# ThrowBot_RX_LED_Board.net
KiCad netlist of a schematic drawn in Altium Designer
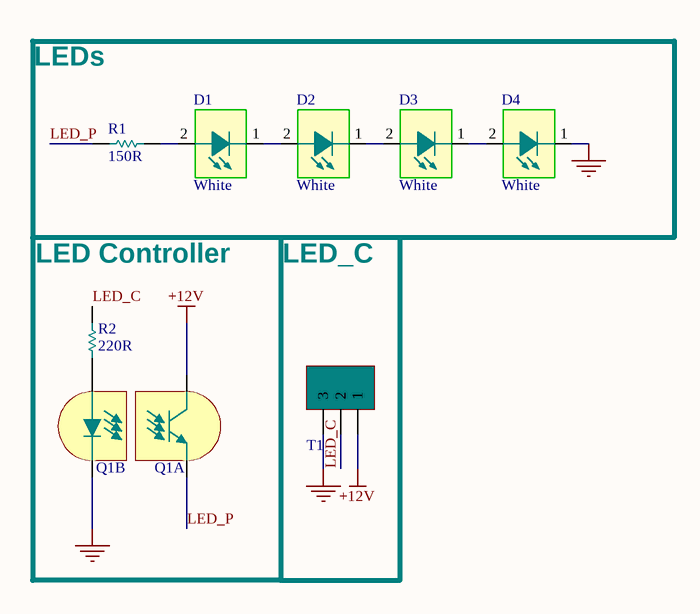
[diagram p0: ThrowBot_RX_LED_Board.SchDoc]

(export (version "E")
  (design (tool "Eeschema 10.0.6"))
  (components
    (comp (ref "D1")
      (value "LED")
      (footprint "LED 3528")
      (fields (field (name "COLOR-4") "White"))
      (libsource (lib "Throwbot") (part "LED"))
    )
    (comp (ref "D2")
      (value "LED")
      (footprint "LED 3528")
      (fields (field (name "COLOR-4") "White"))
      (libsource (lib "Throwbot") (part "LED"))
    )
    (comp (ref "D3")
      (value "LED")
      (footprint "LED 3528")
      (fields (field (name "COLOR-4") "White"))
      (libsource (lib "Throwbot") (part "LED"))
    )
    (comp (ref "D4")
      (value "LED")
      (footprint "LED 3528")
      (fields (field (name "COLOR-4") "White"))
      (libsource (lib "Throwbot") (part "LED"))
    )
    (comp (ref "Q1")
      (value "PC817")
      (footprint "PC817")
      (description "DIP 4pin General Purpose  Photocoupler")
      (libsource (lib "Throwbot") (part "PC817"))
    )
    (comp (ref "R1")
      (value "Resistor")
      (footprint "RES 1206")
      (fields (field (name "VAL-8") "150R"))
      (libsource (lib "Throwbot") (part "Resistor"))
    )
    (comp (ref "R2")
      (value "Resistor")
      (footprint "RES 1206")
      (fields (field (name "VAL-3") "220R"))
      (libsource (lib "Throwbot") (part "Resistor"))
    )
    (comp (ref "T1")
      (value "3 Pin Socket")
      (footprint "XH-3AW")
      (libsource (lib "Throwbot") (part "3 Pin Socket"))
    )
  )
  (nets
    (net (code "1") (name "+12V") (class "Default")
      (node (ref "Q1") (pin "4") (pinfunction "C_4") (pintype "passive"))
      (node (ref "T1") (pin "1") (pinfunction "1_1") (pintype "passive"))
    )
    (net (code "2") (name "/LED_C") (class "Default")
      (node (ref "R2") (pin "2") (pinfunction "2_2") (pintype "passive"))
      (node (ref "T1") (pin "2") (pinfunction "2_2") (pintype "passive"))
    )
    (net (code "3") (name "/LED_P") (class "Default")
      (node (ref "Q1") (pin "3") (pinfunction "E_3") (pintype "passive"))
      (node (ref "R1") (pin "2") (pinfunction "2_2") (pintype "passive"))
    )
    (net (code "4") (name "GND") (class "Default")
      (node (ref "D4") (pin "1") (pinfunction "1_1") (pintype "passive"))
      (node (ref "Q1") (pin "2") (pinfunction "K_2") (pintype "passive"))
      (node (ref "T1") (pin "3") (pinfunction "3_3") (pintype "passive"))
    )
    (net (code "5") (name "Net-(D1-Pad1)") (class "Default")
      (node (ref "D1") (pin "1") (pinfunction "1_1") (pintype "passive"))
      (node (ref "D2") (pin "2") (pinfunction "2_2") (pintype "passive"))
    )
    (net (code "6") (name "Net-(D1-Pad2)") (class "Default")
      (node (ref "D1") (pin "2") (pinfunction "2_2") (pintype "passive"))
      (node (ref "R1") (pin "1") (pinfunction "1_1") (pintype "passive"))
    )
    (net (code "7") (name "Net-(D2-Pad1)") (class "Default")
      (node (ref "D2") (pin "1") (pinfunction "1_1") (pintype "passive"))
      (node (ref "D3") (pin "2") (pinfunction "2_2") (pintype "passive"))
    )
    (net (code "8") (name "Net-(D3-Pad1)") (class "Default")
      (node (ref "D3") (pin "1") (pinfunction "1_1") (pintype "passive"))
      (node (ref "D4") (pin "2") (pinfunction "2_2") (pintype "passive"))
    )
    (net (code "9") (name "Net-(Q1B-A)") (class "Default")
      (node (ref "Q1") (pin "1") (pinfunction "A_1") (pintype "passive"))
      (node (ref "R2") (pin "1") (pinfunction "1_1") (pintype "passive"))
    )
  )
)
